# Pixelart.net
KiCad netlist of a schematic drawn in EasyEDA
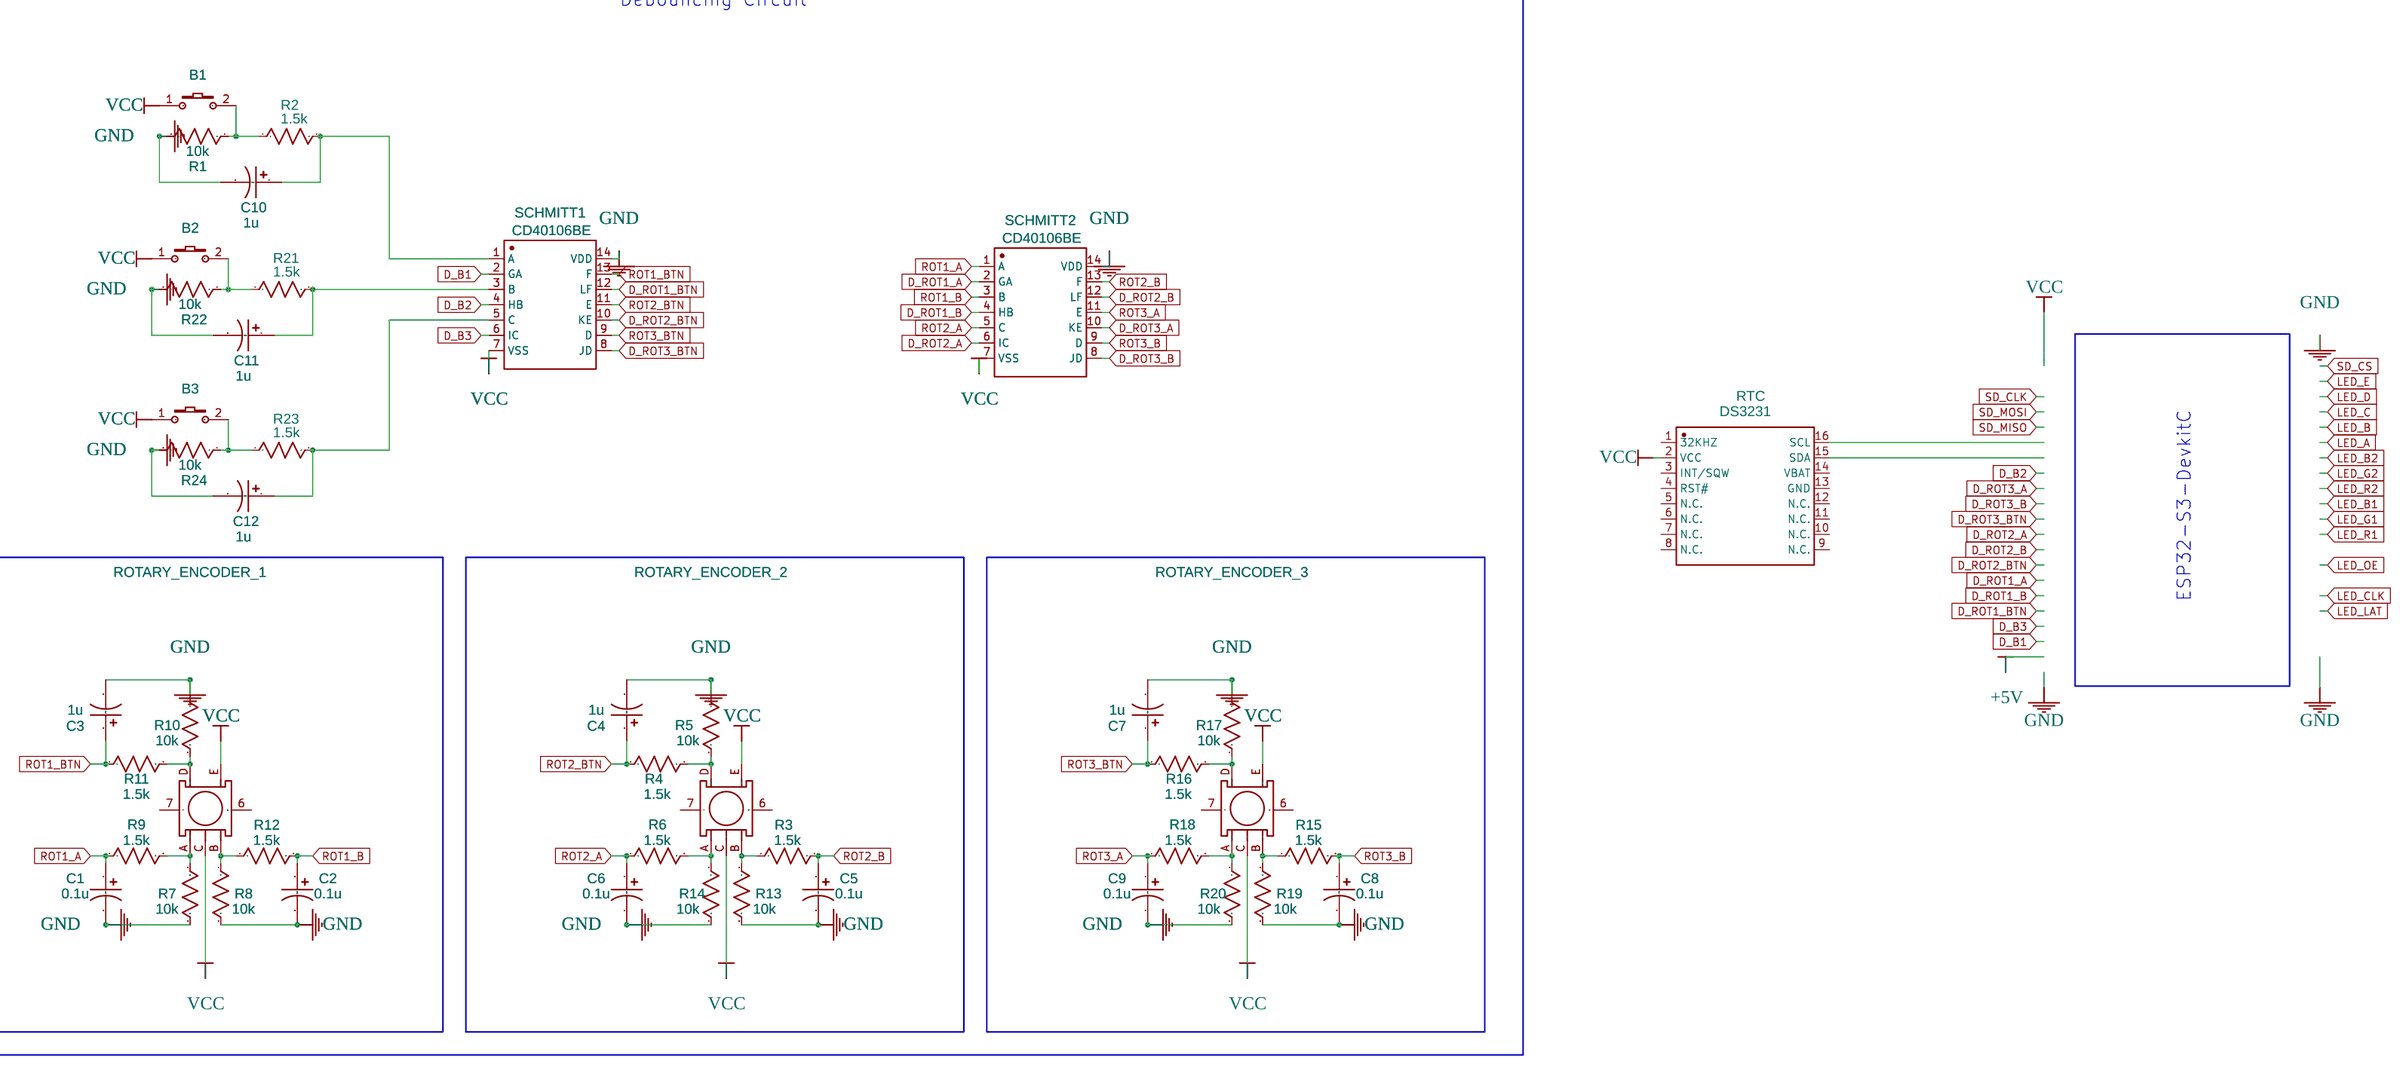
[diagram p0: schematic sheet]

(export (version "E")
  (design (tool "Eeschema 10.0.6"))
  (components
    (comp (ref "C1") (value "0.1u") (libsource (lib "") (part "C_Tan_SMD_A_US")))
    (comp (ref "C2") (value "0.1u") (libsource (lib "") (part "C_Tan_SMD_A_US_2")))
    (comp (ref "C3") (value "1u") (libsource (lib "") (part "C_Tan_SMD_A_US_5")))
    (comp (ref "C4") (value "1u") (libsource (lib "") (part "C_Tan_SMD_A_US_1")))
    (comp (ref "C5") (value "0.1u") (libsource (lib "") (part "C_Tan_SMD_A_US_2")))
    (comp (ref "C6") (value "0.1u") (libsource (lib "") (part "C_Tan_SMD_A_US_2")))
    (comp (ref "C7") (value "1u") (libsource (lib "") (part "C_Tan_SMD_A_US_1")))
    (comp (ref "C8") (value "0.1u") (libsource (lib "") (part "C_Tan_SMD_A_US_2")))
    (comp (ref "C9") (value "0.1u") (libsource (lib "") (part "C_Tan_SMD_A_US_2")))
    (comp (ref "C10") (value "1u") (libsource (lib "") (part "C_Tan_SMD_A_US_4")))
    (comp (ref "C11") (value "1u") (libsource (lib "") (part "C_Tan_SMD_A_US_3")))
    (comp (ref "C12") (value "1u") (libsource (lib "") (part "C_Tan_SMD_A_US_3")))
    (comp (ref "KEY1")
      (value "B1")
      (fields
        (field (name "BOM_Manufacturer Part") "K2-1107ST-A4SW-06")
        (field (name "BOM_Supplier Part") "C118141")
      )
      (libsource (lib "") (part "K2-3.6×6.1_SMD"))
    )
    (comp (ref "KEY2")
      (value "B2")
      (fields
        (field (name "BOM_Manufacturer Part") "K2-1107ST-A4SW-06")
        (field (name "BOM_Supplier Part") "C118141")
      )
      (libsource (lib "") (part "K2-3.6×6.1_SMD"))
    )
    (comp (ref "KEY3")
      (value "B3")
      (fields
        (field (name "BOM_Manufacturer Part") "K2-1107ST-A4SW-06")
        (field (name "BOM_Supplier Part") "C118141")
      )
      (libsource (lib "") (part "K2-3.6×6.1_SMD"))
    )
    (comp (ref "R1") (value "10k") (libsource (lib "") (part "R_0603_US_2")))
    (comp (ref "R2") (value "1.5k") (libsource (lib "") (part "R_0603_US")))
    (comp (ref "R3") (value "1.5k") (libsource (lib "") (part "R_0603_US")))
    (comp (ref "R4") (value "1.5k") (libsource (lib "") (part "R_0603_US")))
    (comp (ref "R5") (value "10k") (libsource (lib "") (part "R_0603_US_1")))
    (comp (ref "R6") (value "1.5k") (libsource (lib "") (part "R_0603_US")))
    (comp (ref "R7") (value "10k") (libsource (lib "") (part "R_0603_US_1")))
    (comp (ref "R8") (value "10k") (libsource (lib "") (part "R_0603_US_1")))
    (comp (ref "R9") (value "1.5k") (libsource (lib "") (part "R_0603_US")))
    (comp (ref "R10") (value "10k") (libsource (lib "") (part "R_0603_US_1")))
    (comp (ref "R11") (value "1.5k") (libsource (lib "") (part "R_0603_US")))
    (comp (ref "R12") (value "1.5k") (libsource (lib "") (part "R_0603_US")))
    (comp (ref "R13") (value "10k") (libsource (lib "") (part "R_0603_US_1")))
    (comp (ref "R14") (value "10k") (libsource (lib "") (part "R_0603_US_1")))
    (comp (ref "R15") (value "1.5k") (libsource (lib "") (part "R_0603_US")))
    (comp (ref "R16") (value "1.5k") (libsource (lib "") (part "R_0603_US")))
    (comp (ref "R17") (value "10k") (libsource (lib "") (part "R_0603_US_1")))
    (comp (ref "R18") (value "1.5k") (libsource (lib "") (part "R_0603_US")))
    (comp (ref "R19") (value "10k") (libsource (lib "") (part "R_0603_US_1")))
    (comp (ref "R20") (value "10k") (libsource (lib "") (part "R_0603_US_1")))
    (comp (ref "R21") (value "1.5k") (libsource (lib "") (part "R_0603_US")))
    (comp (ref "R22") (value "10k") (libsource (lib "") (part "R_0603_US_2")))
    (comp (ref "R23") (value "1.5k") (libsource (lib "") (part "R_0603_US")))
    (comp (ref "R24") (value "10k") (libsource (lib "") (part "R_0603_US_2")))
    (comp (ref "ROTARY_ENCODER_1")
      (value "EC11E15244B2")
      (fields (field (name "BOM_Supplier Part") "C470754"))
      (libsource (lib "") (part "EC11E15244B2"))
    )
    (comp (ref "ROTARY_ENCODER_2")
      (value "EC11E15244B2")
      (fields (field (name "BOM_Supplier Part") "C470754"))
      (libsource (lib "") (part "EC11E15244B2"))
    )
    (comp (ref "ROTARY_ENCODER_3")
      (value "EC11E15244B2")
      (fields (field (name "BOM_Supplier Part") "C470754"))
      (libsource (lib "") (part "EC11E15244B2"))
    )
    (comp (ref "RTC")
      (value "DS3231")
      (fields
        (field (name "BOM_Manufacturer Part") "DS3231N")
        (field (name "BOM_Supplier Part") "C9900010264")
      )
      (libsource (lib "") (part "DS3231N"))
    )
    (comp (ref "SCHMITT1")
      (value "CD40106BE")
      (fields (field (name "BOM_Supplier Part") "C71251"))
      (libsource (lib "") (part "CD40106BE"))
    )
    (comp (ref "SCHMITT2")
      (value "CD40106BE")
      (fields (field (name "BOM_Supplier Part") "C71251"))
      (libsource (lib "") (part "CD40106BE"))
    )
  )
  (nets
    (net (code "2") (name "D_B1") (class "Default")
      (node (ref "SCHMITT1") (pin "2") (pinfunction "GA_2") (pintype "unspecified"))
    )
    (net (code "3") (name "D_B2") (class "Default")
      (node (ref "SCHMITT1") (pin "4") (pinfunction "HB_4") (pintype "unspecified"))
    )
    (net (code "4") (name "D_B3") (class "Default")
      (node (ref "SCHMITT1") (pin "6") (pinfunction "IC_6") (pintype "unspecified"))
    )
    (net (code "5") (name "D_ROT1_A") (class "Default")
      (node (ref "SCHMITT2") (pin "2") (pinfunction "GA_2") (pintype "unspecified"))
    )
    (net (code "6") (name "D_ROT1_B") (class "Default")
      (node (ref "SCHMITT2") (pin "4") (pinfunction "HB_4") (pintype "unspecified"))
    )
    (net (code "7") (name "D_ROT1_BTN") (class "Default")
      (node (ref "SCHMITT1") (pin "12") (pinfunction "LF_12") (pintype "unspecified"))
    )
    (net (code "8") (name "D_ROT2_A") (class "Default")
      (node (ref "SCHMITT2") (pin "6") (pinfunction "IC_6") (pintype "unspecified"))
    )
    (net (code "9") (name "D_ROT2_B") (class "Default")
      (node (ref "SCHMITT2") (pin "12") (pinfunction "LF_12") (pintype "unspecified"))
    )
    (net (code "10") (name "D_ROT2_BTN") (class "Default")
      (node (ref "SCHMITT1") (pin "10") (pinfunction "KE_10") (pintype "unspecified"))
    )
    (net (code "11") (name "D_ROT3_A") (class "Default")
      (node (ref "SCHMITT2") (pin "10") (pinfunction "KE_10") (pintype "unspecified"))
    )
    (net (code "12") (name "D_ROT3_B") (class "Default")
      (node (ref "SCHMITT2") (pin "8") (pinfunction "JD_8") (pintype "unspecified"))
    )
    (net (code "13") (name "D_ROT3_BTN") (class "Default")
      (node (ref "SCHMITT1") (pin "8") (pinfunction "JD_8") (pintype "unspecified"))
    )
    (net (code "14") (name "GND") (class "Default")
      (node (ref "C1") (pin "2") (pinfunction "2_2") (pintype "unspecified"))
      (node (ref "C10") (pin "2") (pinfunction "2_2") (pintype "unspecified"))
      (node (ref "C11") (pin "2") (pinfunction "2_2") (pintype "unspecified"))
      (node (ref "C12") (pin "2") (pinfunction "2_2") (pintype "unspecified"))
      (node (ref "C2") (pin "2") (pinfunction "2_2") (pintype "unspecified"))
      (node (ref "C3") (pin "2") (pinfunction "2_2") (pintype "unspecified"))
      (node (ref "C4") (pin "2") (pinfunction "2_2") (pintype "unspecified"))
      (node (ref "C5") (pin "2") (pinfunction "2_2") (pintype "unspecified"))
      (node (ref "C6") (pin "2") (pinfunction "2_2") (pintype "unspecified"))
      (node (ref "C7") (pin "2") (pinfunction "2_2") (pintype "unspecified"))
      (node (ref "C8") (pin "2") (pinfunction "2_2") (pintype "unspecified"))
      (node (ref "C9") (pin "2") (pinfunction "2_2") (pintype "unspecified"))
      (node (ref "R1") (pin "2") (pinfunction "2_2") (pintype "unspecified"))
      (node (ref "R10") (pin "1") (pinfunction "1_1") (pintype "unspecified"))
      (node (ref "R13") (pin "2") (pinfunction "2_2") (pintype "unspecified"))
      (node (ref "R14") (pin "2") (pinfunction "2_2") (pintype "unspecified"))
      (node (ref "R17") (pin "1") (pinfunction "1_1") (pintype "unspecified"))
      (node (ref "R19") (pin "2") (pinfunction "2_2") (pintype "unspecified"))
      (node (ref "R20") (pin "2") (pinfunction "2_2") (pintype "unspecified"))
      (node (ref "R22") (pin "2") (pinfunction "2_2") (pintype "unspecified"))
      (node (ref "R24") (pin "2") (pinfunction "2_2") (pintype "unspecified"))
      (node (ref "R5") (pin "1") (pinfunction "1_1") (pintype "unspecified"))
      (node (ref "R7") (pin "2") (pinfunction "2_2") (pintype "unspecified"))
      (node (ref "R8") (pin "2") (pinfunction "2_2") (pintype "unspecified"))
      (node (ref "SCHMITT1") (pin "14") (pinfunction "VDD_14") (pintype "unspecified"))
      (node (ref "SCHMITT2") (pin "14") (pinfunction "VDD_14") (pintype "unspecified"))
    )
    (net (code "29") (name "Net-(KEY1-Pad2)") (class "Default")
      (node (ref "KEY1") (pin "2") (pinfunction "2_2") (pintype "unspecified"))
      (node (ref "R1") (pin "1") (pinfunction "1_1") (pintype "unspecified"))
      (node (ref "R2") (pin "1") (pinfunction "1_1") (pintype "unspecified"))
    )
    (net (code "30") (name "Net-(KEY2-Pad2)") (class "Default")
      (node (ref "KEY2") (pin "2") (pinfunction "2_2") (pintype "unspecified"))
      (node (ref "R21") (pin "1") (pinfunction "1_1") (pintype "unspecified"))
      (node (ref "R22") (pin "1") (pinfunction "1_1") (pintype "unspecified"))
    )
    (net (code "31") (name "Net-(KEY3-Pad2)") (class "Default")
      (node (ref "KEY3") (pin "2") (pinfunction "2_2") (pintype "unspecified"))
      (node (ref "R23") (pin "1") (pinfunction "1_1") (pintype "unspecified"))
      (node (ref "R24") (pin "1") (pinfunction "1_1") (pintype "unspecified"))
    )
    (net (code "32") (name "Net-(R4-Pad2)") (class "Default")
      (node (ref "R4") (pin "2") (pinfunction "2_2") (pintype "unspecified"))
      (node (ref "R5") (pin "2") (pinfunction "2_2") (pintype "unspecified"))
      (node (ref "ROTARY_ENCODER_2") (pin "D") (pinfunction "D_D") (pintype "unspecified"))
    )
    (net (code "33") (name "Net-(R7-Pad1)") (class "Default")
      (node (ref "R7") (pin "1") (pinfunction "1_1") (pintype "unspecified"))
      (node (ref "R9") (pin "2") (pinfunction "2_2") (pintype "unspecified"))
      (node (ref "ROTARY_ENCODER_1") (pin "A") (pinfunction "A_A") (pintype "unspecified"))
    )
    (net (code "34") (name "Net-(R10-Pad2)") (class "Default")
      (node (ref "R10") (pin "2") (pinfunction "2_2") (pintype "unspecified"))
      (node (ref "R11") (pin "2") (pinfunction "2_2") (pintype "unspecified"))
      (node (ref "ROTARY_ENCODER_1") (pin "D") (pinfunction "D_D") (pintype "unspecified"))
    )
    (net (code "35") (name "Net-(R12-Pad1)") (class "Default")
      (node (ref "R12") (pin "1") (pinfunction "1_1") (pintype "unspecified"))
      (node (ref "R8") (pin "1") (pinfunction "1_1") (pintype "unspecified"))
      (node (ref "ROTARY_ENCODER_1") (pin "B") (pinfunction "B_B") (pintype "unspecified"))
    )
    (net (code "36") (name "Net-(R13-Pad1)") (class "Default")
      (node (ref "R13") (pin "1") (pinfunction "1_1") (pintype "unspecified"))
      (node (ref "R3") (pin "1") (pinfunction "1_1") (pintype "unspecified"))
      (node (ref "ROTARY_ENCODER_2") (pin "B") (pinfunction "B_B") (pintype "unspecified"))
    )
    (net (code "37") (name "Net-(R14-Pad1)") (class "Default")
      (node (ref "R14") (pin "1") (pinfunction "1_1") (pintype "unspecified"))
      (node (ref "R6") (pin "2") (pinfunction "2_2") (pintype "unspecified"))
      (node (ref "ROTARY_ENCODER_2") (pin "A") (pinfunction "A_A") (pintype "unspecified"))
    )
    (net (code "38") (name "Net-(R15-Pad1)") (class "Default")
      (node (ref "R15") (pin "1") (pinfunction "1_1") (pintype "unspecified"))
      (node (ref "R19") (pin "1") (pinfunction "1_1") (pintype "unspecified"))
      (node (ref "ROTARY_ENCODER_3") (pin "B") (pinfunction "B_B") (pintype "unspecified"))
    )
    (net (code "39") (name "Net-(R16-Pad2)") (class "Default")
      (node (ref "R16") (pin "2") (pinfunction "2_2") (pintype "unspecified"))
      (node (ref "R17") (pin "2") (pinfunction "2_2") (pintype "unspecified"))
      (node (ref "ROTARY_ENCODER_3") (pin "D") (pinfunction "D_D") (pintype "unspecified"))
    )
    (net (code "40") (name "Net-(R18-Pad2)") (class "Default")
      (node (ref "R18") (pin "2") (pinfunction "2_2") (pintype "unspecified"))
      (node (ref "R20") (pin "1") (pinfunction "1_1") (pintype "unspecified"))
      (node (ref "ROTARY_ENCODER_3") (pin "A") (pinfunction "A_A") (pintype "unspecified"))
    )
    (net (code "41") (name "Net-(SCHMITT1-A)") (class "Default")
      (node (ref "C10") (pin "1") (pinfunction "1_1") (pintype "unspecified"))
      (node (ref "R2") (pin "2") (pinfunction "2_2") (pintype "unspecified"))
      (node (ref "SCHMITT1") (pin "1") (pinfunction "A_1") (pintype "unspecified"))
    )
    (net (code "42") (name "Net-(SCHMITT1-B)") (class "Default")
      (node (ref "C11") (pin "1") (pinfunction "1_1") (pintype "unspecified"))
      (node (ref "R21") (pin "2") (pinfunction "2_2") (pintype "unspecified"))
      (node (ref "SCHMITT1") (pin "3") (pinfunction "B_3") (pintype "unspecified"))
    )
    (net (code "43") (name "Net-(SCHMITT1-C)") (class "Default")
      (node (ref "C12") (pin "1") (pinfunction "1_1") (pintype "unspecified"))
      (node (ref "R23") (pin "2") (pinfunction "2_2") (pintype "unspecified"))
      (node (ref "SCHMITT1") (pin "5") (pinfunction "C_5") (pintype "unspecified"))
    )
    (net (code "44") (name "ROT1_A") (class "Default")
      (node (ref "C1") (pin "1") (pinfunction "1_1") (pintype "unspecified"))
      (node (ref "R9") (pin "1") (pinfunction "1_1") (pintype "unspecified"))
      (node (ref "SCHMITT2") (pin "1") (pinfunction "A_1") (pintype "unspecified"))
    )
    (net (code "45") (name "ROT1_B") (class "Default")
      (node (ref "C2") (pin "1") (pinfunction "1_1") (pintype "unspecified"))
      (node (ref "R12") (pin "2") (pinfunction "2_2") (pintype "unspecified"))
      (node (ref "SCHMITT2") (pin "3") (pinfunction "B_3") (pintype "unspecified"))
    )
    (net (code "46") (name "ROT1_BTN") (class "Default")
      (node (ref "C3") (pin "1") (pinfunction "1_1") (pintype "unspecified"))
      (node (ref "R11") (pin "1") (pinfunction "1_1") (pintype "unspecified"))
      (node (ref "SCHMITT1") (pin "13") (pinfunction "F_13") (pintype "unspecified"))
    )
    (net (code "47") (name "ROT2_A") (class "Default")
      (node (ref "C6") (pin "1") (pinfunction "1_1") (pintype "unspecified"))
      (node (ref "R6") (pin "1") (pinfunction "1_1") (pintype "unspecified"))
      (node (ref "SCHMITT2") (pin "5") (pinfunction "C_5") (pintype "unspecified"))
    )
    (net (code "48") (name "ROT2_B") (class "Default")
      (node (ref "C5") (pin "1") (pinfunction "1_1") (pintype "unspecified"))
      (node (ref "R3") (pin "2") (pinfunction "2_2") (pintype "unspecified"))
      (node (ref "SCHMITT2") (pin "13") (pinfunction "F_13") (pintype "unspecified"))
    )
    (net (code "49") (name "ROT2_BTN") (class "Default")
      (node (ref "C4") (pin "1") (pinfunction "1_1") (pintype "unspecified"))
      (node (ref "R4") (pin "1") (pinfunction "1_1") (pintype "unspecified"))
      (node (ref "SCHMITT1") (pin "11") (pinfunction "E_11") (pintype "unspecified"))
    )
    (net (code "50") (name "ROT3_A") (class "Default")
      (node (ref "C9") (pin "1") (pinfunction "1_1") (pintype "unspecified"))
      (node (ref "R18") (pin "1") (pinfunction "1_1") (pintype "unspecified"))
      (node (ref "SCHMITT2") (pin "11") (pinfunction "E_11") (pintype "unspecified"))
    )
    (net (code "51") (name "ROT3_B") (class "Default")
      (node (ref "C8") (pin "1") (pinfunction "1_1") (pintype "unspecified"))
      (node (ref "R15") (pin "2") (pinfunction "2_2") (pintype "unspecified"))
      (node (ref "SCHMITT2") (pin "9") (pinfunction "D_9") (pintype "unspecified"))
    )
    (net (code "52") (name "ROT3_BTN") (class "Default")
      (node (ref "C7") (pin "1") (pinfunction "1_1") (pintype "unspecified"))
      (node (ref "R16") (pin "1") (pinfunction "1_1") (pintype "unspecified"))
      (node (ref "SCHMITT1") (pin "9") (pinfunction "D_9") (pintype "unspecified"))
    )
    (net (code "57") (name "VCC") (class "Default")
      (node (ref "KEY1") (pin "1") (pinfunction "1_1") (pintype "unspecified"))
      (node (ref "KEY2") (pin "1") (pinfunction "1_1") (pintype "unspecified"))
      (node (ref "KEY3") (pin "1") (pinfunction "1_1") (pintype "unspecified"))
      (node (ref "ROTARY_ENCODER_1") (pin "C") (pinfunction "C_C") (pintype "unspecified"))
      (node (ref "ROTARY_ENCODER_1") (pin "E") (pinfunction "E_E") (pintype "unspecified"))
      (node (ref "ROTARY_ENCODER_2") (pin "C") (pinfunction "C_C") (pintype "unspecified"))
      (node (ref "ROTARY_ENCODER_2") (pin "E") (pinfunction "E_E") (pintype "unspecified"))
      (node (ref "ROTARY_ENCODER_3") (pin "C") (pinfunction "C_C") (pintype "unspecified"))
      (node (ref "ROTARY_ENCODER_3") (pin "E") (pinfunction "E_E") (pintype "unspecified"))
      (node (ref "RTC") (pin "2") (pinfunction "VCC_2") (pintype "unspecified"))
      (node (ref "SCHMITT1") (pin "7") (pinfunction "VSS_7") (pintype "unspecified"))
      (node (ref "SCHMITT2") (pin "7") (pinfunction "VSS_7") (pintype "unspecified"))
    )
    (net (code "58") (name "unconnected-(ROTARY_ENCODER_1-Pad6)") (class "Default")
      (node (ref "ROTARY_ENCODER_1") (pin "6") (pinfunction "6_6") (pintype "unspecified"))
    )
    (net (code "59") (name "unconnected-(ROTARY_ENCODER_1-Pad7)") (class "Default")
      (node (ref "ROTARY_ENCODER_1") (pin "7") (pinfunction "7_7") (pintype "unspecified"))
    )
    (net (code "60") (name "unconnected-(ROTARY_ENCODER_2-Pad6)") (class "Default")
      (node (ref "ROTARY_ENCODER_2") (pin "6") (pinfunction "6_6") (pintype "unspecified"))
    )
    (net (code "61") (name "unconnected-(ROTARY_ENCODER_2-Pad7)") (class "Default")
      (node (ref "ROTARY_ENCODER_2") (pin "7") (pinfunction "7_7") (pintype "unspecified"))
    )
    (net (code "62") (name "unconnected-(ROTARY_ENCODER_3-Pad6)") (class "Default")
      (node (ref "ROTARY_ENCODER_3") (pin "6") (pinfunction "6_6") (pintype "unspecified"))
    )
    (net (code "63") (name "unconnected-(ROTARY_ENCODER_3-Pad7)") (class "Default")
      (node (ref "ROTARY_ENCODER_3") (pin "7") (pinfunction "7_7") (pintype "unspecified"))
    )
    (net (code "64") (name "unconnected-(RTC-32KHZ-Pad1)") (class "Default")
      (node (ref "RTC") (pin "1") (pinfunction "32KHZ_1") (pintype "unspecified"))
    )
    (net (code "65") (name "unconnected-(RTC-GND-Pad13)") (class "Default")
      (node (ref "RTC") (pin "13") (pinfunction "GND_13") (pintype "unspecified"))
    )
    (net (code "66") (name "unconnected-(RTC-INT{slash}SQW-Pad3)") (class "Default")
      (node (ref "RTC") (pin "3") (pinfunction "INT/SQW_3") (pintype "unspecified"))
    )
    (net (code "67") (name "unconnected-(RTC-N.C.-Pad5)") (class "Default")
      (node (ref "RTC") (pin "5") (pinfunction "N.C._5") (pintype "unspecified"))
    )
    (net (code "68") (name "unconnected-(RTC-N.C.-Pad6)") (class "Default")
      (node (ref "RTC") (pin "6") (pinfunction "N.C._6") (pintype "unspecified"))
    )
    (net (code "69") (name "unconnected-(RTC-N.C.-Pad7)") (class "Default")
      (node (ref "RTC") (pin "7") (pinfunction "N.C._7") (pintype "unspecified"))
    )
    (net (code "70") (name "unconnected-(RTC-N.C.-Pad8)") (class "Default")
      (node (ref "RTC") (pin "8") (pinfunction "N.C._8") (pintype "unspecified"))
    )
    (net (code "71") (name "unconnected-(RTC-N.C.-Pad9)") (class "Default")
      (node (ref "RTC") (pin "9") (pinfunction "N.C._9") (pintype "unspecified"))
    )
    (net (code "72") (name "unconnected-(RTC-N.C.-Pad10)") (class "Default")
      (node (ref "RTC") (pin "10") (pinfunction "N.C._10") (pintype "unspecified"))
    )
    (net (code "73") (name "unconnected-(RTC-N.C.-Pad11)") (class "Default")
      (node (ref "RTC") (pin "11") (pinfunction "N.C._11") (pintype "unspecified"))
    )
    (net (code "74") (name "unconnected-(RTC-N.C.-Pad12)") (class "Default")
      (node (ref "RTC") (pin "12") (pinfunction "N.C._12") (pintype "unspecified"))
    )
    (net (code "75") (name "unconnected-(RTC-RST#-Pad4)") (class "Default")
      (node (ref "RTC") (pin "4") (pinfunction "RST#_4") (pintype "unspecified"))
    )
    (net (code "76") (name "unconnected-(RTC-SCL-Pad16)") (class "Default")
      (node (ref "RTC") (pin "16") (pinfunction "SCL_16") (pintype "unspecified"))
    )
    (net (code "77") (name "unconnected-(RTC-SDA-Pad15)") (class "Default")
      (node (ref "RTC") (pin "15") (pinfunction "SDA_15") (pintype "unspecified"))
    )
    (net (code "78") (name "unconnected-(RTC-VBAT-Pad14)") (class "Default")
      (node (ref "RTC") (pin "14") (pinfunction "VBAT_14") (pintype "unspecified"))
    )
  )
)
